# untitled.net
KiCad netlist of a schematic drawn in EAGLE
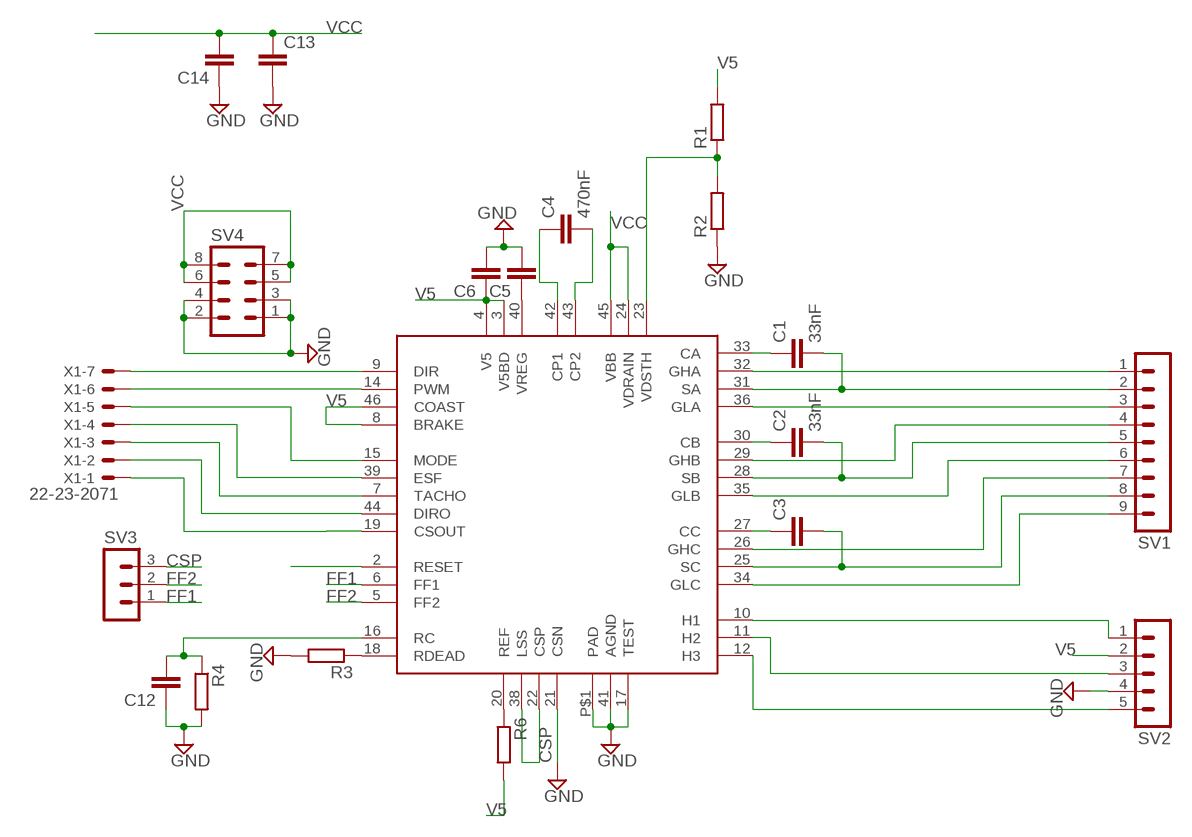
[diagram p0: schematic, sheet 1]

(export (version "E")
  (design (tool "Eeschema 10.0.6"))
  (components
    (comp (ref "C1")
      (value "33nF")
      (footprint "eagle-import:C0603")
      (libsource (lib "eagle-import") (part "C-EUC0603"))
    )
    (comp (ref "C2")
      (value "33nF")
      (footprint "eagle-import:C0603")
      (libsource (lib "eagle-import") (part "C-EUC0603"))
    )
    (comp (ref "C3")
      (value "C-EUC0603")
      (footprint "eagle-import:C0603")
      (libsource (lib "eagle-import") (part "C-EUC0603"))
    )
    (comp (ref "C4")
      (value "470nF")
      (footprint "eagle-import:C0805")
      (libsource (lib "eagle-import") (part "C-EUC0805"))
    )
    (comp (ref "C5")
      (value "C-EUC1206")
      (footprint "eagle-import:C1206")
      (libsource (lib "eagle-import") (part "C-EUC1206"))
    )
    (comp (ref "C6")
      (value "C-EUC1206")
      (footprint "eagle-import:C1206")
      (libsource (lib "eagle-import") (part "C-EUC1206"))
    )
    (comp (ref "C12")
      (value "C-EUC1206")
      (footprint "eagle-import:C1206")
      (libsource (lib "eagle-import") (part "C-EUC1206"))
    )
    (comp (ref "C13")
      (value "C-EU025-050X050")
      (footprint "eagle-import:C025-050X050")
      (libsource (lib "eagle-import") (part "C-EU025-050X050"))
    )
    (comp (ref "C14")
      (value "C-EUC1206")
      (footprint "eagle-import:C1206")
      (libsource (lib "eagle-import") (part "C-EUC1206"))
    )
    (comp (ref "R1")
      (value "R-EU_R1206")
      (footprint "eagle-import:R1206")
      (libsource (lib "eagle-import") (part "R-EU_R1206"))
    )
    (comp (ref "R2")
      (value "R-EU_R1206")
      (footprint "eagle-import:R1206")
      (libsource (lib "eagle-import") (part "R-EU_R1206"))
    )
    (comp (ref "R3")
      (value "R-EU_R1206")
      (footprint "eagle-import:R1206")
      (libsource (lib "eagle-import") (part "R-EU_R1206"))
    )
    (comp (ref "R4")
      (value "R-EU_R1206")
      (footprint "eagle-import:R1206")
      (libsource (lib "eagle-import") (part "R-EU_R1206"))
    )
    (comp (ref "R6")
      (value "R-EU_R1206")
      (footprint "eagle-import:R1206")
      (libsource (lib "eagle-import") (part "R-EU_R1206"))
    )
    (comp (ref "SV1")
      (value "MA09-1")
      (footprint "eagle-import:MA09-1")
      (libsource (lib "eagle-import") (part "MA09-1"))
    )
    (comp (ref "SV2")
      (value "MA05-1")
      (footprint "eagle-import:MA05-1")
      (libsource (lib "eagle-import") (part "MA05-1"))
    )
    (comp (ref "SV3")
      (value "MA03-1")
      (footprint "eagle-import:MA03-1")
      (libsource (lib "eagle-import") (part "MA03-1"))
    )
    (comp (ref "SV4")
      (value "MA04-2")
      (footprint "eagle-import:MA04-2")
      (libsource (lib "eagle-import") (part "MA04-2"))
    )
    (comp (ref "U$1")
      (value "A3930")
      (footprint "eagle-import:TQFP48")
      (libsource (lib "eagle-import") (part "A3930"))
    )
    (comp (ref "X1")
      (value "22-23-2071")
      (footprint "eagle-import:22-23-2071")
      (fields (field (name "MF") "MOLEX"))
      (libsource (lib "eagle-import") (part "22-23-2071"))
    )
  )
  (nets
    (net (code "1") (name "/CSP") (class "Default")
      (node (ref "SV3") (pin "3") (pinfunction "3_3") (pintype "passive"))
      (node (ref "U$1") (pin "22") (pinfunction "CSP_22") (pintype "bidirectional"))
      (node (ref "U$1") (pin "38") (pinfunction "LSS_38") (pintype "bidirectional"))
    )
    (net (code "2") (name "/FF1") (class "Default")
      (node (ref "SV3") (pin "1") (pinfunction "1_1") (pintype "passive"))
      (node (ref "U$1") (pin "6") (pinfunction "FF1_6") (pintype "bidirectional"))
    )
    (net (code "3") (name "/FF2") (class "Default")
      (node (ref "SV3") (pin "2") (pinfunction "2_2") (pintype "passive"))
      (node (ref "U$1") (pin "5") (pinfunction "FF2_5") (pintype "bidirectional"))
    )
    (net (code "4") (name "/V5") (class "Default")
      (node (ref "C6") (pin "1") (pinfunction "1_1") (pintype "passive"))
      (node (ref "R1") (pin "2") (pinfunction "2_2") (pintype "passive"))
      (node (ref "R6") (pin "2") (pinfunction "2_2") (pintype "passive"))
      (node (ref "SV2") (pin "2") (pinfunction "2_2") (pintype "passive"))
      (node (ref "U$1") (pin "3") (pinfunction "V5BD_3") (pintype "bidirectional"))
      (node (ref "U$1") (pin "4") (pinfunction "V5_4") (pintype "bidirectional"))
      (node (ref "U$1") (pin "46") (pinfunction "COAST_46") (pintype "bidirectional"))
      (node (ref "U$1") (pin "8") (pinfunction "BRAKE_8") (pintype "bidirectional"))
    )
    (net (code "5") (name "/VCC") (class "Default")
      (node (ref "C13") (pin "1") (pinfunction "1_1") (pintype "passive"))
      (node (ref "C14") (pin "2") (pinfunction "2_2") (pintype "passive"))
      (node (ref "SV4") (pin "5") (pinfunction "5_5") (pintype "passive"))
      (node (ref "SV4") (pin "6") (pinfunction "6_6") (pintype "passive"))
      (node (ref "SV4") (pin "7") (pinfunction "7_7") (pintype "passive"))
      (node (ref "SV4") (pin "8") (pinfunction "8_8") (pintype "passive"))
      (node (ref "U$1") (pin "24") (pinfunction "VDRAIN_24") (pintype "bidirectional"))
      (node (ref "U$1") (pin "45") (pinfunction "VBB_45") (pintype "bidirectional"))
    )
    (net (code "6") (name "GND") (class "Default")
      (node (ref "C12") (pin "1") (pinfunction "1_1") (pintype "passive"))
      (node (ref "C13") (pin "2") (pinfunction "2_2") (pintype "passive"))
      (node (ref "C14") (pin "1") (pinfunction "1_1") (pintype "passive"))
      (node (ref "C5") (pin "2") (pinfunction "2_2") (pintype "passive"))
      (node (ref "C6") (pin "2") (pinfunction "2_2") (pintype "passive"))
      (node (ref "R2") (pin "1") (pinfunction "1_1") (pintype "passive"))
      (node (ref "R3") (pin "2") (pinfunction "2_2") (pintype "passive"))
      (node (ref "R4") (pin "2") (pinfunction "2_2") (pintype "passive"))
      (node (ref "SV2") (pin "4") (pinfunction "4_4") (pintype "passive"))
      (node (ref "SV4") (pin "1") (pinfunction "1_1") (pintype "passive"))
      (node (ref "SV4") (pin "2") (pinfunction "2_2") (pintype "passive"))
      (node (ref "SV4") (pin "3") (pinfunction "3_3") (pintype "passive"))
      (node (ref "SV4") (pin "4") (pinfunction "4_4") (pintype "passive"))
      (node (ref "U$1") (pin "17") (pinfunction "TEST_17") (pintype "bidirectional"))
      (node (ref "U$1") (pin "21") (pinfunction "CSN_21") (pintype "bidirectional"))
      (node (ref "U$1") (pin "41") (pinfunction "AGND_41") (pintype "bidirectional"))
      (node (ref "U$1") (pin "P$1") (pinfunction "PAD_P$1") (pintype "bidirectional"))
    )
    (net (code "7") (name "Net-(U$1-CA)") (class "Default")
      (node (ref "C1") (pin "1") (pinfunction "1_1") (pintype "passive"))
      (node (ref "U$1") (pin "33") (pinfunction "CA_33") (pintype "bidirectional"))
    )
    (net (code "8") (name "Net-(U$1-CB)") (class "Default")
      (node (ref "C2") (pin "1") (pinfunction "1_1") (pintype "passive"))
      (node (ref "U$1") (pin "30") (pinfunction "CB_30") (pintype "bidirectional"))
    )
    (net (code "9") (name "Net-(U$1-CC)") (class "Default")
      (node (ref "C3") (pin "1") (pinfunction "1_1") (pintype "passive"))
      (node (ref "U$1") (pin "27") (pinfunction "CC_27") (pintype "bidirectional"))
    )
    (net (code "10") (name "Net-(U$1-CP1)") (class "Default")
      (node (ref "C4") (pin "1") (pinfunction "1_1") (pintype "passive"))
      (node (ref "U$1") (pin "42") (pinfunction "CP1_42") (pintype "bidirectional"))
    )
    (net (code "11") (name "Net-(U$1-CP2)") (class "Default")
      (node (ref "C4") (pin "2") (pinfunction "2_2") (pintype "passive"))
      (node (ref "U$1") (pin "43") (pinfunction "CP2_43") (pintype "bidirectional"))
    )
    (net (code "12") (name "Net-(U$1-CSOUT)") (class "Default")
      (node (ref "U$1") (pin "19") (pinfunction "CSOUT_19") (pintype "bidirectional"))
      (node (ref "X1") (pin "1") (pinfunction "S_1") (pintype "passive"))
    )
    (net (code "13") (name "Net-(U$1-DIR)") (class "Default")
      (node (ref "U$1") (pin "9") (pinfunction "DIR_9") (pintype "bidirectional"))
      (node (ref "X1") (pin "7") (pinfunction "S_7") (pintype "passive"))
    )
    (net (code "14") (name "Net-(U$1-DIRO)") (class "Default")
      (node (ref "U$1") (pin "44") (pinfunction "DIRO_44") (pintype "bidirectional"))
      (node (ref "X1") (pin "2") (pinfunction "S_2") (pintype "passive"))
    )
    (net (code "15") (name "Net-(U$1-ESF)") (class "Default")
      (node (ref "U$1") (pin "39") (pinfunction "ESF_39") (pintype "bidirectional"))
      (node (ref "X1") (pin "4") (pinfunction "S_4") (pintype "passive"))
    )
    (net (code "16") (name "Net-(U$1-GHA)") (class "Default")
      (node (ref "SV1") (pin "1") (pinfunction "1_1") (pintype "passive"))
      (node (ref "U$1") (pin "32") (pinfunction "GHA_32") (pintype "bidirectional"))
    )
    (net (code "17") (name "Net-(U$1-GHB)") (class "Default")
      (node (ref "SV1") (pin "4") (pinfunction "4_4") (pintype "passive"))
      (node (ref "U$1") (pin "29") (pinfunction "GHB_29") (pintype "bidirectional"))
    )
    (net (code "18") (name "Net-(U$1-GHC)") (class "Default")
      (node (ref "SV1") (pin "7") (pinfunction "7_7") (pintype "passive"))
      (node (ref "U$1") (pin "26") (pinfunction "GHC_26") (pintype "bidirectional"))
    )
    (net (code "19") (name "Net-(U$1-GLA)") (class "Default")
      (node (ref "SV1") (pin "3") (pinfunction "3_3") (pintype "passive"))
      (node (ref "U$1") (pin "36") (pinfunction "GLA_36") (pintype "bidirectional"))
    )
    (net (code "20") (name "Net-(U$1-GLB)") (class "Default")
      (node (ref "SV1") (pin "6") (pinfunction "6_6") (pintype "passive"))
      (node (ref "U$1") (pin "35") (pinfunction "GLB_35") (pintype "bidirectional"))
    )
    (net (code "21") (name "Net-(U$1-GLC)") (class "Default")
      (node (ref "SV1") (pin "9") (pinfunction "9_9") (pintype "passive"))
      (node (ref "U$1") (pin "34") (pinfunction "GLC_34") (pintype "bidirectional"))
    )
    (net (code "22") (name "Net-(U$1-H1)") (class "Default")
      (node (ref "SV2") (pin "1") (pinfunction "1_1") (pintype "passive"))
      (node (ref "U$1") (pin "10") (pinfunction "H1_10") (pintype "bidirectional"))
    )
    (net (code "23") (name "Net-(U$1-H2)") (class "Default")
      (node (ref "SV2") (pin "3") (pinfunction "3_3") (pintype "passive"))
      (node (ref "U$1") (pin "11") (pinfunction "H2_11") (pintype "bidirectional"))
    )
    (net (code "24") (name "Net-(U$1-H3)") (class "Default")
      (node (ref "SV2") (pin "5") (pinfunction "5_5") (pintype "passive"))
      (node (ref "U$1") (pin "12") (pinfunction "H3_12") (pintype "bidirectional"))
    )
    (net (code "25") (name "Net-(U$1-MODE)") (class "Default")
      (node (ref "U$1") (pin "15") (pinfunction "MODE_15") (pintype "bidirectional"))
      (node (ref "X1") (pin "5") (pinfunction "S_5") (pintype "passive"))
    )
    (net (code "26") (name "Net-(U$1-PWM)") (class "Default")
      (node (ref "U$1") (pin "14") (pinfunction "PWM_14") (pintype "bidirectional"))
      (node (ref "X1") (pin "6") (pinfunction "S_6") (pintype "passive"))
    )
    (net (code "27") (name "Net-(U$1-RC)") (class "Default")
      (node (ref "C12") (pin "2") (pinfunction "2_2") (pintype "passive"))
      (node (ref "R4") (pin "1") (pinfunction "1_1") (pintype "passive"))
      (node (ref "U$1") (pin "16") (pinfunction "RC_16") (pintype "bidirectional"))
    )
    (net (code "28") (name "Net-(U$1-RDEAD)") (class "Default")
      (node (ref "R3") (pin "1") (pinfunction "1_1") (pintype "passive"))
      (node (ref "U$1") (pin "18") (pinfunction "RDEAD_18") (pintype "bidirectional"))
    )
    (net (code "29") (name "Net-(U$1-REF)") (class "Default")
      (node (ref "R6") (pin "1") (pinfunction "1_1") (pintype "passive"))
      (node (ref "U$1") (pin "20") (pinfunction "REF_20") (pintype "bidirectional"))
    )
    (net (code "30") (name "Net-(U$1-SA)") (class "Default")
      (node (ref "C1") (pin "2") (pinfunction "2_2") (pintype "passive"))
      (node (ref "SV1") (pin "2") (pinfunction "2_2") (pintype "passive"))
      (node (ref "U$1") (pin "31") (pinfunction "SA_31") (pintype "bidirectional"))
    )
    (net (code "31") (name "Net-(U$1-SB)") (class "Default")
      (node (ref "C2") (pin "2") (pinfunction "2_2") (pintype "passive"))
      (node (ref "SV1") (pin "5") (pinfunction "5_5") (pintype "passive"))
      (node (ref "U$1") (pin "28") (pinfunction "SB_28") (pintype "bidirectional"))
    )
    (net (code "32") (name "Net-(U$1-SC)") (class "Default")
      (node (ref "C3") (pin "2") (pinfunction "2_2") (pintype "passive"))
      (node (ref "SV1") (pin "8") (pinfunction "8_8") (pintype "passive"))
      (node (ref "U$1") (pin "25") (pinfunction "SC_25") (pintype "bidirectional"))
    )
    (net (code "33") (name "Net-(U$1-TACHO)") (class "Default")
      (node (ref "U$1") (pin "7") (pinfunction "TACHO_7") (pintype "bidirectional"))
      (node (ref "X1") (pin "3") (pinfunction "S_3") (pintype "passive"))
    )
    (net (code "34") (name "Net-(U$1-VDSTH)") (class "Default")
      (node (ref "R1") (pin "1") (pinfunction "1_1") (pintype "passive"))
      (node (ref "R2") (pin "2") (pinfunction "2_2") (pintype "passive"))
      (node (ref "U$1") (pin "23") (pinfunction "VDSTH_23") (pintype "bidirectional"))
    )
    (net (code "35") (name "Net-(U$1-VREG)") (class "Default")
      (node (ref "C5") (pin "1") (pinfunction "1_1") (pintype "passive"))
      (node (ref "U$1") (pin "40") (pinfunction "VREG_40") (pintype "bidirectional"))
    )
    (net (code "36") (name "unconnected-(U$1-RESET-Pad2)") (class "Default")
      (node (ref "U$1") (pin "2") (pinfunction "RESET_2") (pintype "bidirectional"))
    )
  )
)
